# FREENFET3.net
KiCad netlist of a schematic drawn in EAGLE
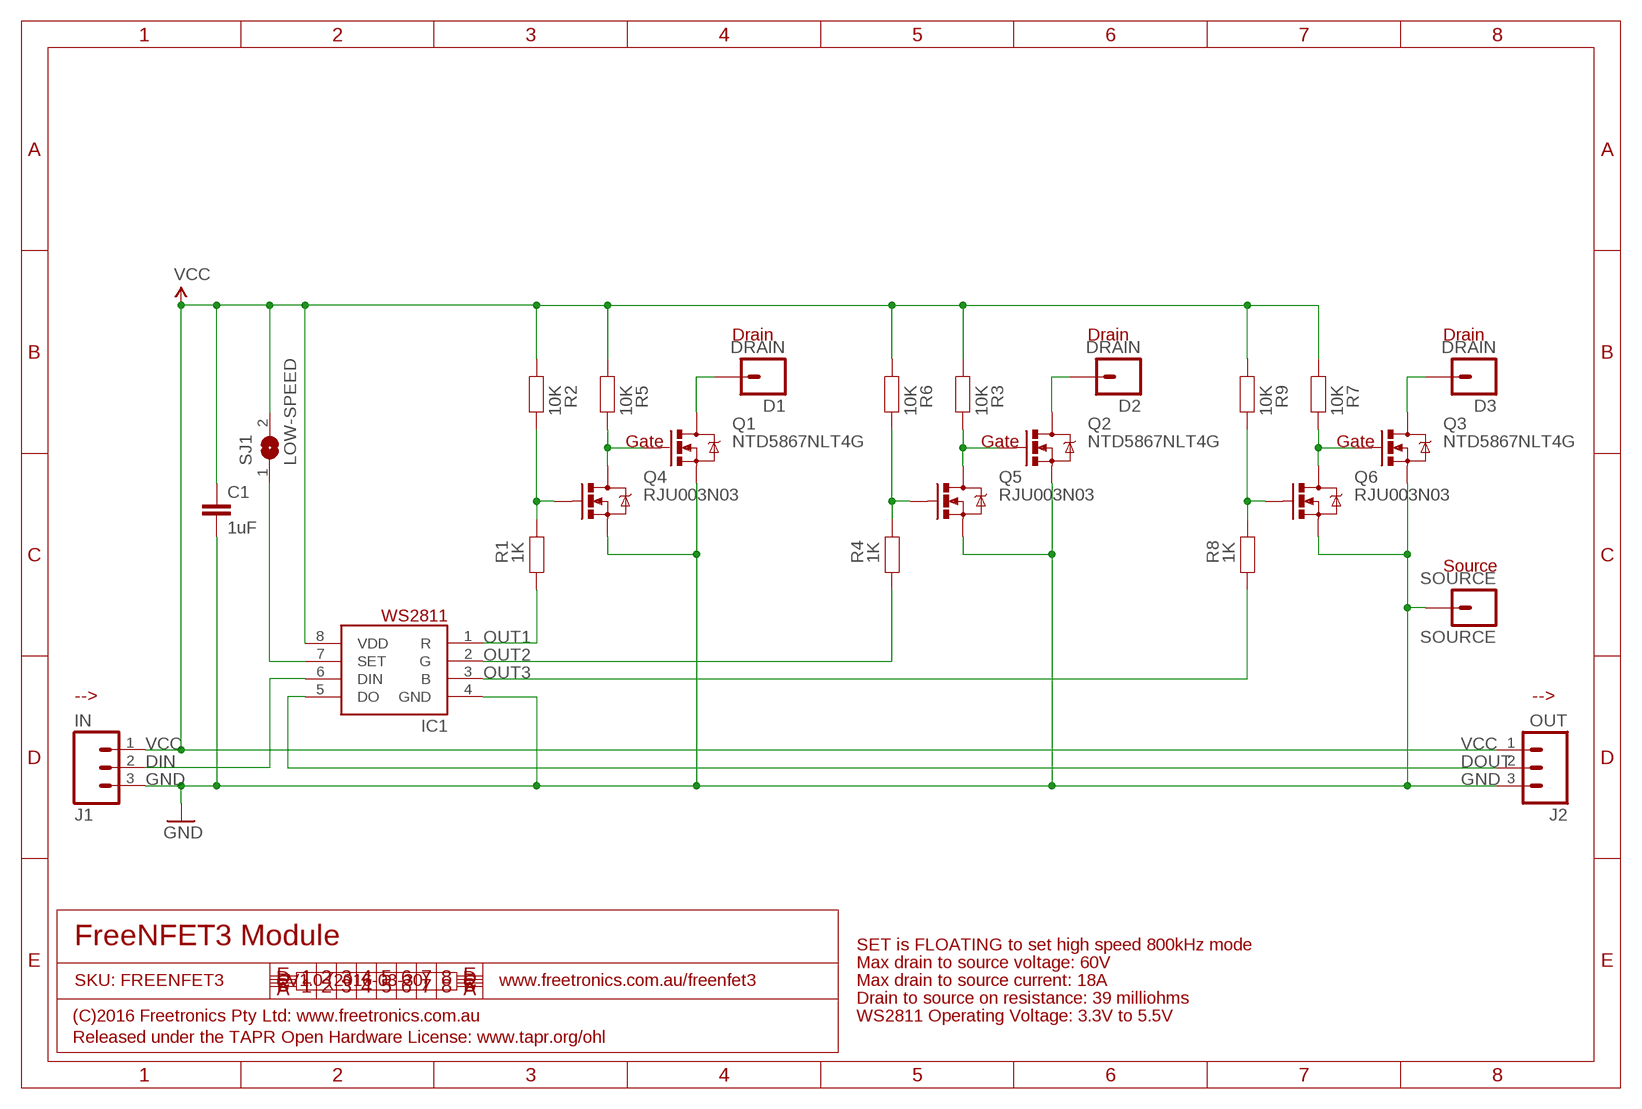
[diagram p0: schematic, sheet 1]

(export (version "E")
  (design (tool "Eeschema 10.0.6"))
  (components
    (comp (ref "C1")
      (value "1uF")
      (footprint "eagle-import:0603")
      (libsource (lib "eagle-import") (part "CAP0603"))
    )
    (comp (ref "D1")
      (value "DRAIN")
      (footprint "eagle-import:1X01LARGE")
      (libsource (lib "eagle-import") (part "M01PTH_LARGE"))
    )
    (comp (ref "D2")
      (value "DRAIN")
      (footprint "eagle-import:1X01LARGE")
      (libsource (lib "eagle-import") (part "M01PTH_LARGE"))
    )
    (comp (ref "D3")
      (value "DRAIN")
      (footprint "eagle-import:1X01LARGE")
      (libsource (lib "eagle-import") (part "M01PTH_LARGE"))
    )
    (comp (ref "IC1")
      (value "WS2811-SOP8")
      (footprint "eagle-import:SO08-SKINNYPADS")
      (libsource (lib "eagle-import") (part "WS2811-SOP8"))
    )
    (comp (ref "J1")
      (value "IN")
      (footprint "eagle-import:1X03")
      (libsource (lib "eagle-import") (part "M03PTH"))
    )
    (comp (ref "J2")
      (value "OUT")
      (footprint "eagle-import:1X03")
      (libsource (lib "eagle-import") (part "M03PTH"))
    )
    (comp (ref "Q1")
      (value "NTD5867NLT4G")
      (footprint "eagle-import:DPACK")
      (libsource (lib "eagle-import") (part "MOSFET-NCHANNELDPAK"))
    )
    (comp (ref "Q2")
      (value "NTD5867NLT4G")
      (footprint "eagle-import:DPACK")
      (libsource (lib "eagle-import") (part "MOSFET-NCHANNELDPAK"))
    )
    (comp (ref "Q3")
      (value "NTD5867NLT4G")
      (footprint "eagle-import:DPACK")
      (libsource (lib "eagle-import") (part "MOSFET-NCHANNELDPAK"))
    )
    (comp (ref "Q4")
      (value "RJU003N03")
      (footprint "eagle-import:SOT32-3")
      (libsource (lib "eagle-import") (part "MOSFET-NSOT-323"))
    )
    (comp (ref "Q5")
      (value "RJU003N03")
      (footprint "eagle-import:SOT32-3")
      (libsource (lib "eagle-import") (part "MOSFET-NSOT-323"))
    )
    (comp (ref "Q6")
      (value "RJU003N03")
      (footprint "eagle-import:SOT32-3")
      (libsource (lib "eagle-import") (part "MOSFET-NSOT-323"))
    )
    (comp (ref "R1")
      (value "1K")
      (footprint "eagle-import:0603")
      (libsource (lib "eagle-import") (part "RESISTOR0603"))
    )
    (comp (ref "R2")
      (value "10K")
      (footprint "eagle-import:0603")
      (libsource (lib "eagle-import") (part "RESISTOR0603"))
    )
    (comp (ref "R3")
      (value "10K")
      (footprint "eagle-import:0603")
      (libsource (lib "eagle-import") (part "RESISTOR0603"))
    )
    (comp (ref "R4")
      (value "1K")
      (footprint "eagle-import:0603")
      (libsource (lib "eagle-import") (part "RESISTOR0603"))
    )
    (comp (ref "R5")
      (value "10K")
      (footprint "eagle-import:0603")
      (libsource (lib "eagle-import") (part "RESISTOR0603"))
    )
    (comp (ref "R6")
      (value "10K")
      (footprint "eagle-import:0603")
      (libsource (lib "eagle-import") (part "RESISTOR0603"))
    )
    (comp (ref "R7")
      (value "10K")
      (footprint "eagle-import:0603")
      (libsource (lib "eagle-import") (part "RESISTOR0603"))
    )
    (comp (ref "R8")
      (value "1K")
      (footprint "eagle-import:0603")
      (libsource (lib "eagle-import") (part "RESISTOR0603"))
    )
    (comp (ref "R9")
      (value "10K")
      (footprint "eagle-import:0603")
      (libsource (lib "eagle-import") (part "RESISTOR0603"))
    )
    (comp (ref "SJ1")
      (value "LOW-SPEED")
      (footprint "eagle-import:SJ")
      (libsource (lib "eagle-import") (part "SJN"))
    )
    (comp (ref "SOURCE")
      (value "SOURCE")
      (footprint "eagle-import:1X01LARGE")
      (libsource (lib "eagle-import") (part "M01PTH_LARGE"))
    )
  )
  (nets
    (net (code "1") (name "/DIN") (class "Default")
      (node (ref "IC1") (pin "6") (pinfunction "DIN_6") (pintype "input"))
      (node (ref "J1") (pin "2") (pinfunction "2_2") (pintype "passive"))
    )
    (net (code "2") (name "/DOUT") (class "Default")
      (node (ref "IC1") (pin "5") (pinfunction "DO_5") (pintype "output"))
      (node (ref "J2") (pin "2") (pinfunction "2_2") (pintype "passive"))
    )
    (net (code "3") (name "/OUT1") (class "Default")
      (node (ref "IC1") (pin "1") (pinfunction "R_1") (pintype "open_collector"))
      (node (ref "R1") (pin "2") (pinfunction "2_2") (pintype "passive"))
    )
    (net (code "4") (name "/OUT2") (class "Default")
      (node (ref "IC1") (pin "2") (pinfunction "G_2") (pintype "open_collector"))
      (node (ref "R4") (pin "2") (pinfunction "2_2") (pintype "passive"))
    )
    (net (code "5") (name "/OUT3") (class "Default")
      (node (ref "IC1") (pin "3") (pinfunction "B_3") (pintype "open_collector"))
      (node (ref "R8") (pin "2") (pinfunction "2_2") (pintype "passive"))
    )
    (net (code "6") (name "GND") (class "Default")
      (node (ref "C1") (pin "2") (pinfunction "2_2") (pintype "passive"))
      (node (ref "IC1") (pin "4") (pinfunction "GND_4") (pintype "power_in"))
      (node (ref "J1") (pin "3") (pinfunction "3_3") (pintype "passive"))
      (node (ref "J2") (pin "3") (pinfunction "3_3") (pintype "passive"))
      (node (ref "Q1") (pin "3") (pinfunction "S_3") (pintype "passive"))
      (node (ref "Q2") (pin "3") (pinfunction "S_3") (pintype "passive"))
      (node (ref "Q3") (pin "3") (pinfunction "S_3") (pintype "passive"))
      (node (ref "Q4") (pin "2") (pinfunction "S_2") (pintype "passive"))
      (node (ref "Q5") (pin "2") (pinfunction "S_2") (pintype "passive"))
      (node (ref "Q6") (pin "2") (pinfunction "S_2") (pintype "passive"))
      (node (ref "SOURCE") (pin "1") (pinfunction "1_1") (pintype "passive"))
    )
    (net (code "7") (name "Net-(IC1-SET)") (class "Default")
      (node (ref "IC1") (pin "7") (pinfunction "SET_7") (pintype "input"))
      (node (ref "SJ1") (pin "1") (pinfunction "1_1") (pintype "passive"))
    )
    (net (code "8") (name "Net-(Q1-D)") (class "Default")
      (node (ref "D1") (pin "1") (pinfunction "1_1") (pintype "passive"))
      (node (ref "Q1") (pin "2") (pinfunction "D_2") (pintype "passive"))
    )
    (net (code "9") (name "Net-(Q1-G)") (class "Default")
      (node (ref "Q1") (pin "1") (pinfunction "G_1") (pintype "passive"))
      (node (ref "Q4") (pin "3") (pinfunction "D_3") (pintype "passive"))
      (node (ref "R5") (pin "1") (pinfunction "1_1") (pintype "passive"))
    )
    (net (code "10") (name "Net-(Q2-D)") (class "Default")
      (node (ref "D2") (pin "1") (pinfunction "1_1") (pintype "passive"))
      (node (ref "Q2") (pin "2") (pinfunction "D_2") (pintype "passive"))
    )
    (net (code "11") (name "Net-(Q2-G)") (class "Default")
      (node (ref "Q2") (pin "1") (pinfunction "G_1") (pintype "passive"))
      (node (ref "Q5") (pin "3") (pinfunction "D_3") (pintype "passive"))
      (node (ref "R3") (pin "1") (pinfunction "1_1") (pintype "passive"))
    )
    (net (code "12") (name "Net-(Q3-D)") (class "Default")
      (node (ref "D3") (pin "1") (pinfunction "1_1") (pintype "passive"))
      (node (ref "Q3") (pin "2") (pinfunction "D_2") (pintype "passive"))
    )
    (net (code "13") (name "Net-(Q3-G)") (class "Default")
      (node (ref "Q3") (pin "1") (pinfunction "G_1") (pintype "passive"))
      (node (ref "Q6") (pin "3") (pinfunction "D_3") (pintype "passive"))
      (node (ref "R7") (pin "1") (pinfunction "1_1") (pintype "passive"))
    )
    (net (code "14") (name "Net-(Q4-G)") (class "Default")
      (node (ref "Q4") (pin "1") (pinfunction "G_1") (pintype "passive"))
      (node (ref "R1") (pin "1") (pinfunction "1_1") (pintype "passive"))
      (node (ref "R2") (pin "1") (pinfunction "1_1") (pintype "passive"))
    )
    (net (code "15") (name "Net-(Q5-G)") (class "Default")
      (node (ref "Q5") (pin "1") (pinfunction "G_1") (pintype "passive"))
      (node (ref "R4") (pin "1") (pinfunction "1_1") (pintype "passive"))
      (node (ref "R6") (pin "1") (pinfunction "1_1") (pintype "passive"))
    )
    (net (code "16") (name "Net-(Q6-G)") (class "Default")
      (node (ref "Q6") (pin "1") (pinfunction "G_1") (pintype "passive"))
      (node (ref "R8") (pin "1") (pinfunction "1_1") (pintype "passive"))
      (node (ref "R9") (pin "1") (pinfunction "1_1") (pintype "passive"))
    )
    (net (code "17") (name "VCC") (class "Default")
      (node (ref "C1") (pin "1") (pinfunction "1_1") (pintype "passive"))
      (node (ref "IC1") (pin "8") (pinfunction "VDD_8") (pintype "power_in"))
      (node (ref "J1") (pin "1") (pinfunction "1_1") (pintype "passive"))
      (node (ref "J2") (pin "1") (pinfunction "1_1") (pintype "passive"))
      (node (ref "R2") (pin "2") (pinfunction "2_2") (pintype "passive"))
      (node (ref "R3") (pin "2") (pinfunction "2_2") (pintype "passive"))
      (node (ref "R5") (pin "2") (pinfunction "2_2") (pintype "passive"))
      (node (ref "R6") (pin "2") (pinfunction "2_2") (pintype "passive"))
      (node (ref "R7") (pin "2") (pinfunction "2_2") (pintype "passive"))
      (node (ref "R9") (pin "2") (pinfunction "2_2") (pintype "passive"))
      (node (ref "SJ1") (pin "2") (pinfunction "2_2") (pintype "passive"))
    )
  )
)
